# tomu-eagle-easy.net
KiCad netlist of a schematic drawn in EAGLE
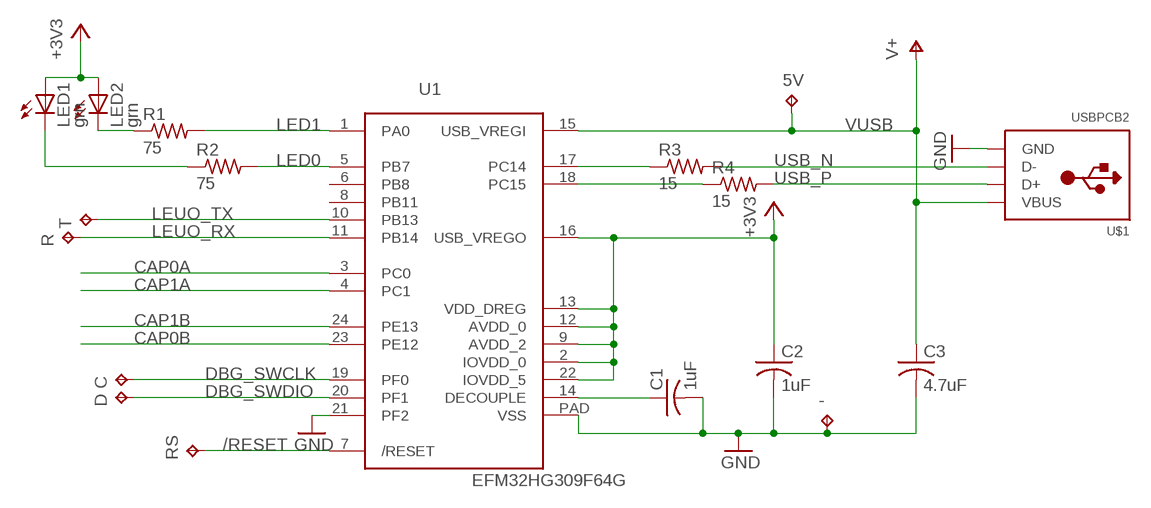
[diagram p0: schematic, sheet 1]

(export (version "E")
  (design (tool "Eeschema 10.0.6"))
  (components
    (comp (ref "-")
      (value "TPTP10SQ")
      (footprint "eagle-import:TP10SQ")
      (libsource (lib "eagle-import") (part "TPTP10SQ"))
    )
    (comp (ref "5V")
      (value "TPTP10R")
      (footprint "eagle-import:TP10R")
      (libsource (lib "eagle-import") (part "TPTP10R"))
    )
    (comp (ref "C")
      (value "TPTP10R")
      (footprint "eagle-import:TP10R")
      (libsource (lib "eagle-import") (part "TPTP10R"))
    )
    (comp (ref "C1")
      (value "1uF")
      (footprint "eagle-import:C0402K")
      (libsource (lib "eagle-import") (part "C-USC0402K"))
    )
    (comp (ref "C2")
      (value "1uF")
      (footprint "eagle-import:C0402")
      (libsource (lib "eagle-import") (part "C-USC0402"))
    )
    (comp (ref "C3")
      (value "4.7uF")
      (footprint "eagle-import:C0402")
      (libsource (lib "eagle-import") (part "C-USC0402"))
    )
    (comp (ref "D")
      (value "TPTP10R")
      (footprint "eagle-import:TP10R")
      (libsource (lib "eagle-import") (part "TPTP10R"))
    )
    (comp (ref "LED1")
      (value "grn")
      (footprint "eagle-import:CHIP-LED0603")
      (libsource (lib "eagle-import") (part "LEDCHIP-LED0603"))
    )
    (comp (ref "LED2")
      (value "grn")
      (footprint "eagle-import:CHIP-LED0603")
      (libsource (lib "eagle-import") (part "LEDCHIP-LED0603"))
    )
    (comp (ref "R")
      (value "TPTP10R")
      (footprint "eagle-import:TP10R")
      (libsource (lib "eagle-import") (part "TPTP10R"))
    )
    (comp (ref "R1")
      (value "75")
      (footprint "eagle-import:R0402")
      (libsource (lib "eagle-import") (part "R-US_R0402"))
    )
    (comp (ref "R2")
      (value "75")
      (footprint "eagle-import:R0402")
      (libsource (lib "eagle-import") (part "R-US_R0402"))
    )
    (comp (ref "R3")
      (value "15")
      (footprint "eagle-import:R0402")
      (libsource (lib "eagle-import") (part "R-US_R0402"))
    )
    (comp (ref "R4")
      (value "15")
      (footprint "eagle-import:R0402")
      (libsource (lib "eagle-import") (part "R-US_R0402"))
    )
    (comp (ref "RS")
      (value "TPTP10R")
      (footprint "eagle-import:TP10R")
      (libsource (lib "eagle-import") (part "TPTP10R"))
    )
    (comp (ref "T")
      (value "TPTP10R")
      (footprint "eagle-import:TP10R")
      (libsource (lib "eagle-import") (part "TPTP10R"))
    )
    (comp (ref "U$1")
      (value "USBPCB2")
      (footprint "eagle-import:USB-A-PCB-2")
      (libsource (lib "eagle-import") (part "USBPCB2"))
    )
    (comp (ref "U1")
      (value "EFM32HG309F64G")
      (footprint "eagle-import:QFN24PAD")
      (libsource (lib "eagle-import") (part "EFM32HG309F64G"))
    )
  )
  (nets
    (net (code "1") (name "+3V3") (class "Default")
      (node (ref "C2") (pin "1") (pinfunction "1_1") (pintype "passive"))
      (node (ref "LED1") (pin "A") (pinfunction "A_A") (pintype "passive"))
      (node (ref "LED2") (pin "A") (pinfunction "A_A") (pintype "passive"))
      (node (ref "U1") (pin "12") (pinfunction "AVDD_0_12") (pintype "bidirectional"))
      (node (ref "U1") (pin "13") (pinfunction "VDD_DREG_13") (pintype "bidirectional"))
      (node (ref "U1") (pin "16") (pinfunction "USB_VREGO_16") (pintype "bidirectional"))
      (node (ref "U1") (pin "2") (pinfunction "IOVDD_0_2") (pintype "bidirectional"))
      (node (ref "U1") (pin "22") (pinfunction "IOVDD_5_22") (pintype "bidirectional"))
      (node (ref "U1") (pin "9") (pinfunction "AVDD_2_9") (pintype "bidirectional"))
    )
    (net (code "2") (name "/CAP0A") (class "Default")
      (node (ref "U1") (pin "3") (pinfunction "PC0_3") (pintype "bidirectional"))
    )
    (net (code "3") (name "/CAP0B") (class "Default")
      (node (ref "U1") (pin "23") (pinfunction "PE12_23") (pintype "bidirectional"))
    )
    (net (code "4") (name "/CAP1A") (class "Default")
      (node (ref "U1") (pin "4") (pinfunction "PC1_4") (pintype "bidirectional"))
    )
    (net (code "5") (name "/CAP1B") (class "Default")
      (node (ref "U1") (pin "24") (pinfunction "PE13_24") (pintype "bidirectional"))
    )
    (net (code "6") (name "/DBG_SWCLK") (class "Default")
      (node (ref "C") (pin "TP") (pinfunction "TP_TP") (pintype "input"))
      (node (ref "U1") (pin "19") (pinfunction "PF0_19") (pintype "bidirectional"))
    )
    (net (code "7") (name "/DBG_SWDIO") (class "Default")
      (node (ref "D") (pin "TP") (pinfunction "TP_TP") (pintype "input"))
      (node (ref "U1") (pin "20") (pinfunction "PF1_20") (pintype "bidirectional"))
    )
    (net (code "8") (name "/LED0") (class "Default")
      (node (ref "R2") (pin "2") (pinfunction "2_2") (pintype "passive"))
      (node (ref "U1") (pin "5") (pinfunction "PB7_5") (pintype "bidirectional"))
    )
    (net (code "9") (name "/LED1") (class "Default")
      (node (ref "R1") (pin "2") (pinfunction "2_2") (pintype "passive"))
      (node (ref "U1") (pin "1") (pinfunction "PA0_1") (pintype "bidirectional"))
    )
    (net (code "10") (name "/LEUO_RX") (class "Default")
      (node (ref "R") (pin "TP") (pinfunction "TP_TP") (pintype "input"))
      (node (ref "U1") (pin "11") (pinfunction "PB14_11") (pintype "bidirectional"))
    )
    (net (code "11") (name "/LEUO_TX") (class "Default")
      (node (ref "T") (pin "TP") (pinfunction "TP_TP") (pintype "input"))
      (node (ref "U1") (pin "10") (pinfunction "PB13_10") (pintype "bidirectional"))
    )
    (net (code "12") (name "/USB_N") (class "Default")
      (node (ref "R3") (pin "2") (pinfunction "2_2") (pintype "passive"))
      (node (ref "U$1") (pin "USB_M") (pinfunction "D-_USB_M") (pintype "bidirectional"))
    )
    (net (code "13") (name "/USB_P") (class "Default")
      (node (ref "R4") (pin "2") (pinfunction "2_2") (pintype "passive"))
      (node (ref "U$1") (pin "USB_P") (pinfunction "D+_USB_P") (pintype "bidirectional"))
    )
    (net (code "14") (name "/{slash}RESET") (class "Default")
      (node (ref "RS") (pin "TP") (pinfunction "TP_TP") (pintype "input"))
      (node (ref "U1") (pin "7") (pinfunction "/RESET_7") (pintype "bidirectional"))
    )
    (net (code "15") (name "GND") (class "Default")
      (node (ref "-") (pin "TP") (pinfunction "TP_TP") (pintype "input"))
      (node (ref "C1") (pin "2") (pinfunction "2_2") (pintype "passive"))
      (node (ref "C2") (pin "2") (pinfunction "2_2") (pintype "passive"))
      (node (ref "C3") (pin "2") (pinfunction "2_2") (pintype "passive"))
      (node (ref "U$1") (pin "GND") (pinfunction "GND_GND") (pintype "power_in"))
      (node (ref "U1") (pin "21") (pinfunction "PF2_21") (pintype "bidirectional"))
      (node (ref "U1") (pin "PAD") (pinfunction "VSS_PAD") (pintype "bidirectional"))
    )
    (net (code "16") (name "Net-(LED1-PadC)") (class "Default")
      (node (ref "LED1") (pin "C") (pinfunction "C_C") (pintype "passive"))
      (node (ref "R2") (pin "1") (pinfunction "1_1") (pintype "passive"))
    )
    (net (code "17") (name "Net-(LED2-PadC)") (class "Default")
      (node (ref "LED2") (pin "C") (pinfunction "C_C") (pintype "passive"))
      (node (ref "R1") (pin "1") (pinfunction "1_1") (pintype "passive"))
    )
    (net (code "18") (name "Net-(U1-DECOUPLE)") (class "Default")
      (node (ref "C1") (pin "1") (pinfunction "1_1") (pintype "passive"))
      (node (ref "U1") (pin "14") (pinfunction "DECOUPLE_14") (pintype "bidirectional"))
    )
    (net (code "19") (name "Net-(U1-PC14)") (class "Default")
      (node (ref "R3") (pin "1") (pinfunction "1_1") (pintype "passive"))
      (node (ref "U1") (pin "17") (pinfunction "PC14_17") (pintype "bidirectional"))
    )
    (net (code "20") (name "Net-(U1-PC15)") (class "Default")
      (node (ref "R4") (pin "1") (pinfunction "1_1") (pintype "passive"))
      (node (ref "U1") (pin "18") (pinfunction "PC15_18") (pintype "bidirectional"))
    )
    (net (code "21") (name "V+") (class "Default")
      (node (ref "5V") (pin "TP") (pinfunction "TP_TP") (pintype "input"))
      (node (ref "C3") (pin "1") (pinfunction "1_1") (pintype "passive"))
      (node (ref "U$1") (pin "5V") (pinfunction "VBUS_5V") (pintype "power_in"))
      (node (ref "U1") (pin "15") (pinfunction "USB_VREGI_15") (pintype "bidirectional"))
    )
    (net (code "22") (name "unconnected-(U1-PB8-Pad6)") (class "Default")
      (node (ref "U1") (pin "6") (pinfunction "PB8_6") (pintype "bidirectional"))
    )
    (net (code "23") (name "unconnected-(U1-PB11-Pad8)") (class "Default")
      (node (ref "U1") (pin "8") (pinfunction "PB11_8") (pintype "bidirectional"))
    )
  )
)
